# 2022.net
KiCad netlist of a schematic drawn in Altium Designer
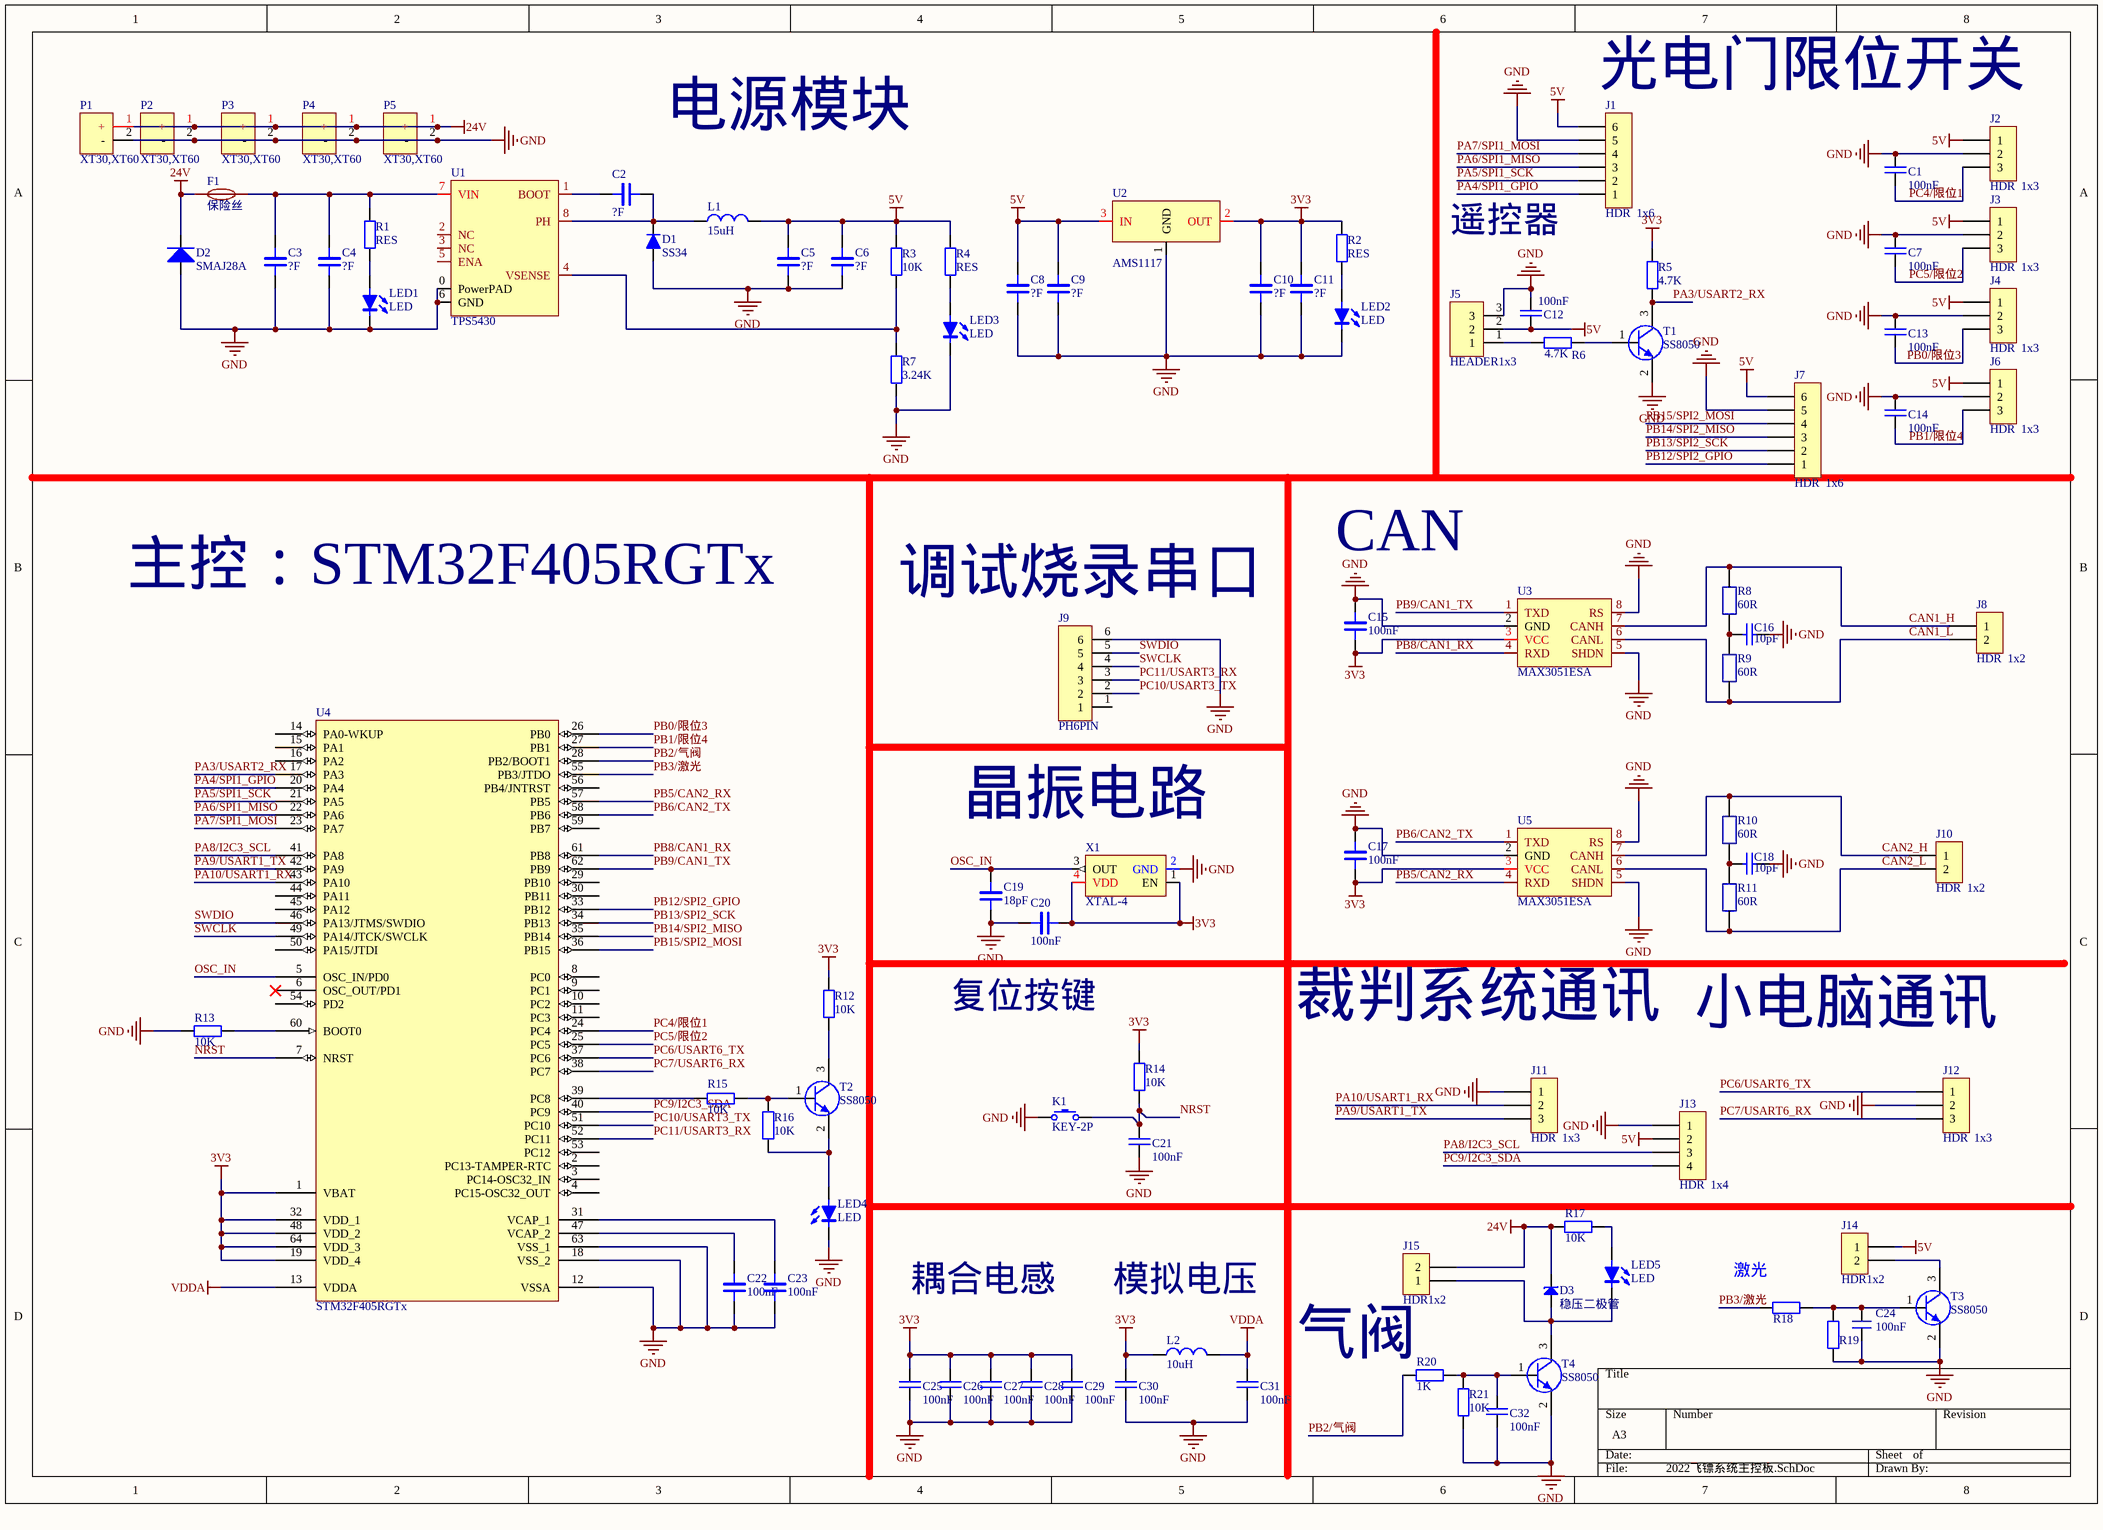
[diagram p0: 2022飞镖系统主控板.SchDoc]

(export (version "E")
  (design (tool "Eeschema 10.0.6"))
  (components
    (comp (ref "C1")
      (value "100nF")
      (footprint "0603_C")
      (fields (field (name "PUBLISHER") "Altium Limited"))
      (libsource (lib "电容-电阻-电感") (part "Cap"))
    )
    (comp (ref "C2")
      (value "?F")
      (footprint "0603_C")
      (description "Capacitor")
      (libsource (lib "General（旧）") (part "CAP"))
    )
    (comp (ref "C3")
      (value "?F")
      (footprint "1206_C")
      (description "Capacitor")
      (libsource (lib "General（旧）") (part "CAP"))
    )
    (comp (ref "C4")
      (value "?F")
      (footprint "1206_C")
      (description "Capacitor")
      (libsource (lib "General（旧）") (part "CAP"))
    )
    (comp (ref "C5")
      (value "?F")
      (footprint "1206_C")
      (description "Capacitor")
      (libsource (lib "General（旧）") (part "CAP"))
    )
    (comp (ref "C6")
      (value "?F")
      (footprint "1206_C")
      (description "Capacitor")
      (libsource (lib "General（旧）") (part "CAP"))
    )
    (comp (ref "C7")
      (value "100nF")
      (footprint "0603_C")
      (fields (field (name "PUBLISHER") "Altium Limited"))
      (libsource (lib "电容-电阻-电感") (part "Cap"))
    )
    (comp (ref "C8")
      (value "?F")
      (footprint "1206_C")
      (description "Capacitor")
      (libsource (lib "General（旧）") (part "CAP"))
    )
    (comp (ref "C9")
      (value "?F")
      (footprint "1206_C")
      (description "Capacitor")
      (libsource (lib "General（旧）") (part "CAP"))
    )
    (comp (ref "C10")
      (value "?F")
      (footprint "1206_C")
      (description "Capacitor")
      (libsource (lib "General（旧）") (part "CAP"))
    )
    (comp (ref "C11")
      (value "?F")
      (footprint "1206_C")
      (description "Capacitor")
      (libsource (lib "General（旧）") (part "CAP"))
    )
    (comp (ref "C12")
      (value "100nF")
      (footprint "0603_C")
      (fields (field (name "PUBLISHER") "Altium Limited"))
      (libsource (lib "电容-电阻-电感") (part "Cap"))
    )
    (comp (ref "C13")
      (value "100nF")
      (footprint "0603_C")
      (fields (field (name "PUBLISHER") "Altium Limited"))
      (libsource (lib "电容-电阻-电感") (part "Cap"))
    )
    (comp (ref "C14")
      (value "100nF")
      (footprint "0603_C")
      (fields (field (name "PUBLISHER") "Altium Limited"))
      (libsource (lib "电容-电阻-电感") (part "Cap"))
    )
    (comp (ref "C15")
      (value "100nF")
      (footprint "0603_C")
      (description "Capacitor")
      (libsource (lib "General（旧）") (part "CAP"))
    )
    (comp (ref "C16") (value "10pF") (footprint "0603_C") (libsource (lib "原理图库") (part "C")))
    (comp (ref "C17")
      (value "100nF")
      (footprint "0603_C")
      (description "Capacitor")
      (libsource (lib "General（旧）") (part "CAP"))
    )
    (comp (ref "C18") (value "10pF") (footprint "0603_C") (libsource (lib "原理图库") (part "C")))
    (comp (ref "C19")
      (value "18pF")
      (footprint "0603_C")
      (description "Capacitor")
      (libsource (lib "General（旧）") (part "CAP"))
    )
    (comp (ref "C20")
      (value "100nF")
      (footprint "0603_C")
      (description "Capacitor")
      (libsource (lib "General（旧）") (part "CAP"))
    )
    (comp (ref "C21")
      (value "100nF")
      (footprint "0603_C")
      (fields (field (name "PUBLISHER") "Altium Limited"))
      (libsource (lib "电容-电阻-电感") (part "Cap"))
    )
    (comp (ref "C22")
      (value "100nF")
      (footprint "0603_C")
      (description "Capacitor")
      (libsource (lib "General（旧）") (part "CAP"))
    )
    (comp (ref "C23")
      (value "100nF")
      (footprint "0603_C")
      (description "Capacitor")
      (libsource (lib "General（旧）") (part "CAP"))
    )
    (comp (ref "C24")
      (value "100nF")
      (footprint "0603_C")
      (fields (field (name "PUBLISHER") "Altium Limited"))
      (libsource (lib "USUAUL") (part "Cap"))
    )
    (comp (ref "C25")
      (value "100nF")
      (footprint "0603_C")
      (fields (field (name "PUBLISHER") "Altium Limited"))
      (libsource (lib "电容-电阻-电感") (part "Cap"))
    )
    (comp (ref "C26")
      (value "100nF")
      (footprint "0603_C")
      (fields (field (name "PUBLISHER") "Altium Limited"))
      (libsource (lib "电容-电阻-电感") (part "Cap"))
    )
    (comp (ref "C27")
      (value "100nF")
      (footprint "0603_C")
      (fields (field (name "PUBLISHER") "Altium Limited"))
      (libsource (lib "电容-电阻-电感") (part "Cap"))
    )
    (comp (ref "C28")
      (value "100nF")
      (footprint "0603_C")
      (fields (field (name "PUBLISHER") "Altium Limited"))
      (libsource (lib "电容-电阻-电感") (part "Cap"))
    )
    (comp (ref "C29")
      (value "100nF")
      (footprint "0603_C")
      (fields (field (name "PUBLISHER") "Altium Limited"))
      (libsource (lib "电容-电阻-电感") (part "Cap"))
    )
    (comp (ref "C30")
      (value "100nF")
      (footprint "0603_C")
      (fields (field (name "PUBLISHER") "Altium Limited"))
      (libsource (lib "电容-电阻-电感") (part "Cap"))
    )
    (comp (ref "C31")
      (value "100nF")
      (footprint "0603_C")
      (fields (field (name "PUBLISHER") "Altium Limited"))
      (libsource (lib "电容-电阻-电感") (part "Cap"))
    )
    (comp (ref "C32")
      (value "100nF")
      (footprint "0603_C")
      (fields (field (name "PUBLISHER") "Altium Limited"))
      (libsource (lib "电容-电阻-电感") (part "Cap"))
    )
    (comp (ref "D1")
      (value "SS34")
      (footprint "SMA(DO-214AC)")
      (description "肖特基二极管")
      (fields
        (field (name "BOM_SUPPLIER PART") "C431540")
        (field (name "BOM_MANUFACTURER PART") "MSK12C02")
        (field (name "CONTRIBUTOR") "LCSC")
      )
      (libsource (lib "General（旧）") (part "SS34"))
    )
    (comp (ref "D2")
      (value "SMAJ28A")
      (footprint "SMA(DO-214AC)")
      (description "TVS")
      (libsource (lib "General（旧）") (part "SMAJ28A"))
    )
    (comp (ref "D3") (value "稳压二极管") (footprint "SOD-323") (libsource (lib "General（旧）") (part "稳压二极管")))
    (comp (ref "F1") (value "保险丝") (footprint "1812_F") (libsource (lib "General（旧）") (part "保险丝")))
    (comp (ref "J1")
      (value "HDR  1x6")
      (footprint "GH 6P 1.25mm 卧 贴")
      (description "Connector")
      (libsource (lib "General（旧）") (part "HDR  1x6"))
    )
    (comp (ref "J2")
      (value "HDR  1x3")
      (footprint "PH 3P 2mm 立 插")
      (description "Connector")
      (libsource (lib "General（旧）") (part "HDR  1x3"))
    )
    (comp (ref "J3")
      (value "HDR  1x3")
      (footprint "PH 3P 2mm 立 插")
      (description "Connector")
      (libsource (lib "General（旧）") (part "HDR  1x3"))
    )
    (comp (ref "J4")
      (value "HDR  1x3")
      (footprint "PH 3P 2mm 立 插")
      (description "Connector")
      (libsource (lib "General（旧）") (part "HDR  1x3"))
    )
    (comp (ref "J5")
      (value "HEADER1x3")
      (footprint "GH 3P 1.25mm 卧 贴")
      (libsource (lib "连接器") (part "HEADER1x3"))
    )
    (comp (ref "J6")
      (value "HDR  1x3")
      (footprint "PH 3P 2mm 立 插")
      (description "Connector")
      (libsource (lib "General（旧）") (part "HDR  1x3"))
    )
    (comp (ref "J7")
      (value "HDR  1x6")
      (footprint "GH 6P 1.25mm 卧 贴")
      (description "Connector")
      (libsource (lib "General（旧）") (part "HDR  1x6"))
    )
    (comp (ref "J8")
      (value "HDR  1x2")
      (footprint "GH 2P 1.25mm 卧 贴")
      (description "Connector")
      (libsource (lib "General（旧）") (part "HDR  1x2"))
    )
    (comp (ref "J9") (value "PH6PIN") (footprint "PH 6P 2mm 立 插") (libsource (lib "连接器") (part "PH 6P")))
    (comp (ref "J10")
      (value "HDR  1x2")
      (footprint "GH 2P 1.25mm 卧 贴")
      (description "Connector")
      (libsource (lib "General（旧）") (part "HDR  1x2"))
    )
    (comp (ref "J11")
      (value "HDR  1x3")
      (footprint "GH 3P 1.25mm 卧 贴")
      (description "Connector")
      (libsource (lib "General（旧）") (part "HDR  1x3"))
    )
    (comp (ref "J12")
      (value "HDR  1x3")
      (footprint "PH 3P 2mm 卧 贴")
      (description "Connector")
      (libsource (lib "General（旧）") (part "HDR  1x3"))
    )
    (comp (ref "J13")
      (value "HDR  1x4")
      (footprint "排针排母 4P 2.54mm")
      (description "Connector")
      (libsource (lib "General（旧）") (part "HDR  1x4"))
    )
    (comp (ref "J14")
      (value "HDR1x2")
      (footprint "PH 2P 2mm 立 贴")
      (description "Connector")
      (libsource (lib "") (part "HDR1x2_1"))
    )
    (comp (ref "J15")
      (value "HDR1x2")
      (footprint "PH 2P 2mm 立 贴")
      (description "Connector")
      (libsource (lib "General") (part "HDR1x2"))
    )
    (comp (ref "K1")
      (value "KEY-2P")
      (footprint "SW-按键")
      (description "Key")
      (libsource (lib "General") (part "KEY-2P"))
    )
    (comp (ref "L1")
      (value "15uH")
      (footprint "SMD_7.3*6.6*3MM_0630")
      (description "Inductor")
      (fields (field (name "PUBLISHER") "Altium Limited"))
      (libsource (lib "General（旧）") (part "Inductor"))
    )
    (comp (ref "L2")
      (value "10uH")
      (footprint "0603_L")
      (description "Inductor")
      (fields (field (name "PUBLISHER") "Altium Limited"))
      (libsource (lib "General（旧）") (part "Inductor"))
    )
    (comp (ref "LED1") (value "LED") (footprint "LED_0603") (libsource (lib "General（旧）") (part "LED")))
    (comp (ref "LED2") (value "LED") (footprint "LED_0603") (libsource (lib "General（旧）") (part "LED")))
    (comp (ref "LED3") (value "LED") (footprint "LED_0603") (libsource (lib "General（旧）") (part "LED")))
    (comp (ref "LED4") (value "LED") (footprint "LED_0603") (libsource (lib "General（旧）") (part "LED")))
    (comp (ref "LED5") (value "LED") (footprint "LED_0603") (libsource (lib "General（旧）") (part "LED")))
    (comp (ref "P1")
      (value "XT30,XT60")
      (footprint "XT30PW-F")
      (description "电源接口")
      (libsource (lib "General（旧）") (part "XT"))
    )
    (comp (ref "P2")
      (value "XT30,XT60")
      (footprint "XT30PW-F")
      (description "电源接口")
      (libsource (lib "General（旧）") (part "XT"))
    )
    (comp (ref "P3")
      (value "XT30,XT60")
      (footprint "XT30PW-F")
      (description "电源接口")
      (libsource (lib "General（旧）") (part "XT"))
    )
    (comp (ref "P4")
      (value "XT30,XT60")
      (footprint "XT30PW-F")
      (description "电源接口")
      (libsource (lib "General（旧）") (part "XT"))
    )
    (comp (ref "P5")
      (value "XT30,XT60")
      (footprint "XT30PW-F")
      (description "电源接口")
      (libsource (lib "General（旧）") (part "XT"))
    )
    (comp (ref "R1")
      (value "RES")
      (footprint "0603_R")
      (description "Resistor")
      (libsource (lib "") (part "RES_1"))
    )
    (comp (ref "R2")
      (value "RES")
      (footprint "0603_R")
      (description "Resistor")
      (libsource (lib "") (part "RES_1"))
    )
    (comp (ref "R3")
      (value "10K")
      (footprint "0603_R")
      (description "Resistor")
      (libsource (lib "") (part "RES_1"))
    )
    (comp (ref "R4")
      (value "RES")
      (footprint "0603_R")
      (description "Resistor")
      (libsource (lib "") (part "RES_1"))
    )
    (comp (ref "R5")
      (value "4.7K")
      (footprint "0603_R")
      (fields (field (name "PUBLISHER") "Altium Limited"))
      (libsource (lib "电容-电阻-电感") (part "Res"))
    )
    (comp (ref "R6")
      (value "4.7K")
      (footprint "0603_R")
      (fields (field (name "PUBLISHER") "Altium Limited"))
      (libsource (lib "") (part "Res_2"))
    )
    (comp (ref "R7")
      (value "3.24K")
      (footprint "0603_R")
      (description "Resistor")
      (libsource (lib "") (part "RES_1"))
    )
    (comp (ref "R8") (value "60R") (footprint "0603_R") (libsource (lib "原理图库") (part "R")))
    (comp (ref "R9") (value "60R") (footprint "0603_R") (libsource (lib "原理图库") (part "R")))
    (comp (ref "R10") (value "60R") (footprint "0603_R") (libsource (lib "原理图库") (part "R")))
    (comp (ref "R11") (value "60R") (footprint "0603_R") (libsource (lib "原理图库") (part "R")))
    (comp (ref "R12")
      (value "10K")
      (footprint "0603_R")
      (description "Resistor")
      (libsource (lib "") (part "RES_2"))
    )
    (comp (ref "R13")
      (value "10K")
      (footprint "0603_R")
      (description "Resistor")
      (libsource (lib "") (part "RES_3"))
    )
    (comp (ref "R14")
      (value "10K")
      (footprint "0603_R")
      (fields (field (name "PUBLISHER") "Altium Limited"))
      (libsource (lib "电容-电阻-电感") (part "Res"))
    )
    (comp (ref "R15")
      (value "10K")
      (footprint "0603_R")
      (description "Resistor")
      (libsource (lib "General（旧）") (part "RES"))
    )
    (comp (ref "R16")
      (value "10K")
      (footprint "0603_R")
      (description "Resistor")
      (libsource (lib "") (part "RES_3"))
    )
    (comp (ref "R17")
      (value "10K")
      (footprint "0603_R")
      (fields (field (name "PUBLISHER") "Altium Limited"))
      (libsource (lib "") (part "Res_1"))
    )
    (comp (ref "R18")
      (value "Res")
      (footprint "0603_R")
      (fields (field (name "PUBLISHER") "Altium Limited"))
      (libsource (lib "") (part "Res_1"))
    )
    (comp (ref "R19")
      (value "Res")
      (footprint "0603_R")
      (fields (field (name "PUBLISHER") "Altium Limited"))
      (libsource (lib "电容-电阻-电感") (part "Res"))
    )
    (comp (ref "R20")
      (value "1K")
      (footprint "0603_R")
      (fields (field (name "PUBLISHER") "Altium Limited"))
      (libsource (lib "") (part "Res_1"))
    )
    (comp (ref "R21")
      (value "10K")
      (footprint "0603_R")
      (fields (field (name "PUBLISHER") "Altium Limited"))
      (libsource (lib "电容-电阻-电感") (part "Res"))
    )
    (comp (ref "T1")
      (value "SS8050")
      (footprint "SOT-23")
      (description "NPN")
      (fields (field (name "PUBLISHER") "Altium Limited"))
      (libsource (lib "二极管-晶体管") (part "SS8050"))
    )
    (comp (ref "T2")
      (value "SS8050")
      (footprint "SOT-23")
      (description "NPN")
      (fields (field (name "PUBLISHER") "Altium Limited"))
      (libsource (lib "二极管-晶体管") (part "SS8050"))
    )
    (comp (ref "T3")
      (value "SS8050")
      (footprint "SOT-23")
      (description "NPN")
      (fields (field (name "PUBLISHER") "Altium Limited"))
      (libsource (lib "二极管-晶体管") (part "SS8050"))
    )
    (comp (ref "T4")
      (value "SS8050")
      (footprint "SOT-23")
      (description "NPN")
      (fields (field (name "PUBLISHER") "Altium Limited"))
      (libsource (lib "二极管-晶体管") (part "SS8050"))
    )
    (comp (ref "U1")
      (value "TPS5430")
      (footprint "SOP8-EP")
      (description "DC-DC 降压芯片")
      (libsource (lib "General（旧）") (part "TPS5430"))
    )
    (comp (ref "U2")
      (value "AMS1117")
      (footprint "SOT-223")
      (description "LDO")
      (libsource (lib "General（旧）") (part "AMS1117"))
    )
    (comp (ref "U3")
      (value "MAX3051ESA")
      (footprint "SOP8")
      (description "CAN芯片")
      (libsource (lib "General（旧）") (part "MAX3051ESA"))
    )
    (comp (ref "U4")
      (value "STM32F405RGTx")
      (footprint "LQFP-64_10x10x05P")
      (description "STM32单片机")
      (libsource (lib "General（旧）") (part "STM32F405RGTx"))
    )
    (comp (ref "U5")
      (value "MAX3051ESA")
      (footprint "SOP8")
      (description "CAN芯片")
      (libsource (lib "General（旧）") (part "MAX3051ESA"))
    )
    (comp (ref "X1")
      (value "XTAL-4")
      (footprint "OSC-SMD_4P")
      (description "Oscillator")
      (libsource (lib "General（旧）") (part "XTAL-4"))
    )
  )
  (nets
    (net (code "1") (name "/CAN1_H") (class "Default")
      (node (ref "J8") (pin "1") (pinfunction "1_1") (pintype "passive"))
      (node (ref "R8") (pin "2") (pinfunction "2_2") (pintype "passive"))
      (node (ref "U3") (pin "7") (pinfunction "CANH_7") (pintype "passive"))
    )
    (net (code "2") (name "/CAN1_L") (class "Default")
      (node (ref "J8") (pin "2") (pinfunction "2_2") (pintype "passive"))
      (node (ref "R9") (pin "2") (pinfunction "2_2") (pintype "passive"))
      (node (ref "U3") (pin "6") (pinfunction "CANL_6") (pintype "passive"))
    )
    (net (code "3") (name "/CAN2_H") (class "Default")
      (node (ref "J10") (pin "1") (pinfunction "1_1") (pintype "passive"))
      (node (ref "R10") (pin "2") (pinfunction "2_2") (pintype "passive"))
      (node (ref "U5") (pin "7") (pinfunction "CANH_7") (pintype "passive"))
    )
    (net (code "4") (name "/CAN2_L") (class "Default")
      (node (ref "J10") (pin "2") (pinfunction "2_2") (pintype "passive"))
      (node (ref "R11") (pin "2") (pinfunction "2_2") (pintype "passive"))
      (node (ref "U5") (pin "6") (pinfunction "CANL_6") (pintype "passive"))
    )
    (net (code "5") (name "/NRST") (class "Default")
      (node (ref "C21") (pin "1") (pinfunction "1_1") (pintype "passive"))
      (node (ref "K1") (pin "2") (pinfunction "2_2") (pintype "passive"))
      (node (ref "R14") (pin "1") (pinfunction "1_1") (pintype "passive"))
      (node (ref "U4") (pin "7") (pinfunction "NRST_7") (pintype "bidirectional"))
    )
    (net (code "6") (name "/OSC_IN") (class "Default")
      (node (ref "C19") (pin "2") (pinfunction "2_2") (pintype "passive"))
      (node (ref "U4") (pin "5") (pinfunction "OSC_IN/PD0_5") (pintype "passive"))
      (node (ref "X1") (pin "3") (pinfunction "OUT_3") (pintype "output"))
    )
    (net (code "7") (name "/PA3{slash}USART2_RX") (class "Default")
      (node (ref "R5") (pin "1") (pinfunction "1_1") (pintype "passive"))
      (node (ref "T1") (pin "3") (pinfunction "C_3") (pintype "passive"))
      (node (ref "U4") (pin "17") (pinfunction "PA3_17") (pintype "bidirectional"))
    )
    (net (code "8") (name "/PA4{slash}SPI1_GPIO") (class "Default")
      (node (ref "J1") (pin "1") (pinfunction "1_1") (pintype "passive"))
      (node (ref "U4") (pin "20") (pinfunction "PA4_20") (pintype "bidirectional"))
    )
    (net (code "9") (name "/PA5{slash}SPI1_SCK") (class "Default")
      (node (ref "J1") (pin "2") (pinfunction "2_2") (pintype "passive"))
      (node (ref "U4") (pin "21") (pinfunction "PA5_21") (pintype "bidirectional"))
    )
    (net (code "10") (name "/PA6{slash}SPI1_MISO") (class "Default")
      (node (ref "J1") (pin "3") (pinfunction "3_3") (pintype "passive"))
      (node (ref "U4") (pin "22") (pinfunction "PA6_22") (pintype "bidirectional"))
    )
    (net (code "11") (name "/PA7{slash}SPI1_MOSI") (class "Default")
      (node (ref "J1") (pin "4") (pinfunction "4_4") (pintype "passive"))
      (node (ref "U4") (pin "23") (pinfunction "PA7_23") (pintype "bidirectional"))
    )
    (net (code "12") (name "/PA8{slash}I2C3_SCL") (class "Default")
      (node (ref "J13") (pin "3") (pinfunction "3_3") (pintype "passive"))
      (node (ref "U4") (pin "41") (pinfunction "PA8_41") (pintype "bidirectional"))
    )
    (net (code "13") (name "/PA9{slash}USART1_TX") (class "Default")
      (node (ref "J11") (pin "3") (pinfunction "3_3") (pintype "passive"))
      (node (ref "U4") (pin "42") (pinfunction "PA9_42") (pintype "bidirectional"))
    )
    (net (code "14") (name "/PA10{slash}USART1_RX") (class "Default")
      (node (ref "J11") (pin "2") (pinfunction "2_2") (pintype "passive"))
      (node (ref "U4") (pin "43") (pinfunction "PA10_43") (pintype "bidirectional"))
    )
    (net (code "15") (name "/PB0{slash}限位3") (class "Default")
      (node (ref "C13") (pin "2") (pinfunction "2_2") (pintype "passive"))
      (node (ref "J4") (pin "3") (pinfunction "3_3") (pintype "passive"))
      (node (ref "U4") (pin "26") (pinfunction "PB0_26") (pintype "bidirectional"))
    )
    (net (code "16") (name "/PB1{slash}限位4") (class "Default")
      (node (ref "C14") (pin "2") (pinfunction "2_2") (pintype "passive"))
      (node (ref "J6") (pin "3") (pinfunction "3_3") (pintype "passive"))
      (node (ref "U4") (pin "27") (pinfunction "PB1_27") (pintype "bidirectional"))
    )
    (net (code "17") (name "/PB2{slash}气阀") (class "Default")
      (node (ref "R20") (pin "1") (pinfunction "1_1") (pintype "passive"))
      (node (ref "U4") (pin "28") (pinfunction "PB2/BOOT1_28") (pintype "bidirectional"))
    )
    (net (code "18") (name "/PB3{slash}激光") (class "Default")
      (node (ref "R18") (pin "1") (pinfunction "1_1") (pintype "passive"))
      (node (ref "U4") (pin "55") (pinfunction "PB3/JTDO_55") (pintype "bidirectional"))
    )
    (net (code "19") (name "/PB5{slash}CAN2_RX") (class "Default")
      (node (ref "U4") (pin "57") (pinfunction "PB5_57") (pintype "bidirectional"))
      (node (ref "U5") (pin "4") (pinfunction "RXD_4") (pintype "passive"))
    )
    (net (code "20") (name "/PB6{slash}CAN2_TX") (class "Default")
      (node (ref "U4") (pin "58") (pinfunction "PB6_58") (pintype "bidirectional"))
      (node (ref "U5") (pin "1") (pinfunction "TXD_1") (pintype "passive"))
    )
    (net (code "21") (name "/PB8{slash}CAN1_RX") (class "Default")
      (node (ref "U3") (pin "4") (pinfunction "RXD_4") (pintype "passive"))
      (node (ref "U4") (pin "61") (pinfunction "PB8_61") (pintype "bidirectional"))
    )
    (net (code "22") (name "/PB9{slash}CAN1_TX") (class "Default")
      (node (ref "U3") (pin "1") (pinfunction "TXD_1") (pintype "passive"))
      (node (ref "U4") (pin "62") (pinfunction "PB9_62") (pintype "bidirectional"))
    )
    (net (code "23") (name "/PB12{slash}SPI2_GPIO") (class "Default")
      (node (ref "J7") (pin "1") (pinfunction "1_1") (pintype "passive"))
      (node (ref "U4") (pin "33") (pinfunction "PB12_33") (pintype "bidirectional"))
    )
    (net (code "24") (name "/PB13{slash}SPI2_SCK") (class "Default")
      (node (ref "J7") (pin "2") (pinfunction "2_2") (pintype "passive"))
      (node (ref "U4") (pin "34") (pinfunction "PB13_34") (pintype "bidirectional"))
    )
    (net (code "25") (name "/PB14{slash}SPI2_MISO") (class "Default")
      (node (ref "J7") (pin "3") (pinfunction "3_3") (pintype "passive"))
      (node (ref "U4") (pin "35") (pinfunction "PB14_35") (pintype "bidirectional"))
    )
    (net (code "26") (name "/PB15{slash}SPI2_MOSI") (class "Default")
      (node (ref "J7") (pin "4") (pinfunction "4_4") (pintype "passive"))
      (node (ref "U4") (pin "36") (pinfunction "PB15_36") (pintype "bidirectional"))
    )
    (net (code "27") (name "/PC4{slash}限位1") (class "Default")
      (node (ref "C1") (pin "2") (pinfunction "2_2") (pintype "passive"))
      (node (ref "J2") (pin "3") (pinfunction "3_3") (pintype "passive"))
      (node (ref "U4") (pin "24") (pinfunction "PC4_24") (pintype "bidirectional"))
    )
    (net (code "28") (name "/PC5{slash}限位2") (class "Default")
      (node (ref "C7") (pin "2") (pinfunction "2_2") (pintype "passive"))
      (node (ref "J3") (pin "3") (pinfunction "3_3") (pintype "passive"))
      (node (ref "U4") (pin "25") (pinfunction "PC5_25") (pintype "bidirectional"))
    )
    (net (code "29") (name "/PC6{slash}USART6_TX") (class "Default")
      (node (ref "J12") (pin "1") (pinfunction "1_1") (pintype "passive"))
      (node (ref "U4") (pin "37") (pinfunction "PC6_37") (pintype "bidirectional"))
    )
    (net (code "30") (name "/PC7{slash}USART6_RX") (class "Default")
      (node (ref "J12") (pin "3") (pinfunction "3_3") (pintype "passive"))
      (node (ref "U4") (pin "38") (pinfunction "PC7_38") (pintype "bidirectional"))
    )
    (net (code "31") (name "/PC9{slash}I2C3_SDA") (class "Default")
      (node (ref "J13") (pin "4") (pinfunction "4_4") (pintype "passive"))
      (node (ref "U4") (pin "40") (pinfunction "PC9_40") (pintype "bidirectional"))
    )
    (net (code "32") (name "/PC10{slash}USART3_TX") (class "Default")
      (node (ref "J9") (pin "2") (pinfunction "2_2") (pintype "passive"))
      (node (ref "U4") (pin "51") (pinfunction "PC10_51") (pintype "bidirectional"))
    )
    (net (code "33") (name "/PC11{slash}USART3_RX") (class "Default")
      (node (ref "J9") (pin "3") (pinfunction "3_3") (pintype "passive"))
      (node (ref "U4") (pin "52") (pinfunction "PC11_52") (pintype "bidirectional"))
    )
    (net (code "34") (name "/SWCLK") (class "Default")
      (node (ref "J9") (pin "4") (pinfunction "4_4") (pintype "passive"))
      (node (ref "U4") (pin "49") (pinfunction "PA14/JTCK/SWCLK_49") (pintype "bidirectional"))
    )
    (net (code "35") (name "/SWDIO") (class "Default")
      (node (ref "J9") (pin "5") (pinfunction "5_5") (pintype "passive"))
      (node (ref "U4") (pin "46") (pinfunction "PA13/JTMS/SWDIO_46") (pintype "bidirectional"))
    )
    (net (code "36") (name "3V3") (class "Default")
      (node (ref "C10") (pin "2") (pinfunction "2_2") (pintype "passive"))
      (node (ref "C11") (pin "2") (pinfunction "2_2") (pintype "passive"))
      (node (ref "C15") (pin "2") (pinfunction "2_2") (pintype "passive"))
      (node (ref "C17") (pin "2") (pinfunction "2_2") (pintype "passive"))
      (node (ref "C20") (pin "2") (pinfunction "2_2") (pintype "passive"))
      (node (ref "C25") (pin "1") (pinfunction "1_1") (pintype "passive"))
      (node (ref "C26") (pin "1") (pinfunction "1_1") (pintype "passive"))
      (node (ref "C27") (pin "1") (pinfunction "1_1") (pintype "passive"))
      (node (ref "C28") (pin "1") (pinfunction "1_1") (pintype "passive"))
      (node (ref "C29") (pin "1") (pinfunction "1_1") (pintype "passive"))
      (node (ref "C30") (pin "1") (pinfunction "1_1") (pintype "passive"))
      (node (ref "L2") (pin "1") (pinfunction "1_1") (pintype "passive"))
      (node (ref "R12") (pin "1") (pinfunction "1_1") (pintype "passive"))
      (node (ref "R14") (pin "2") (pinfunction "2_2") (pintype "passive"))
      (node (ref "R2") (pin "2") (pinfunction "2_2") (pintype "passive"))
      (node (ref "R5") (pin "2") (pinfunction "2_2") (pintype "passive"))
      (node (ref "U2") (pin "2") (pinfunction "OUT_2") (pintype "passive"))
      (node (ref "U3") (pin "3") (pinfunction "VCC_3") (pintype "passive"))
      (node (ref "U4") (pin "1") (pinfunction "VBAT_1") (pintype "power_in"))
      (node (ref "U4") (pin "19") (pinfunction "VDD_4_19") (pintype "power_in"))
      (node (ref "U4") (pin "32") (pinfunction "VDD_1_32") (pintype "power_in"))
      (node (ref "U4") (pin "48") (pinfunction "VDD_2_48") (pintype "power_in"))
      (node (ref "U4") (pin "64") (pinfunction "VDD_3_64") (pintype "power_in"))
      (node (ref "U5") (pin "3") (pinfunction "VCC_3") (pintype "passive"))
      (node (ref "X1") (pin "1") (pinfunction "EN_1") (pintype "passive"))
      (node (ref "X1") (pin "4") (pinfunction "VDD_4") (pintype "power_in"))
    )
    (net (code "37") (name "5V") (class "Default")
      (node (ref "C12") (pin "1") (pinfunction "1_1") (pintype "passive"))
      (node (ref "C5") (pin "2") (pinfunction "2_2") (pintype "passive"))
      (node (ref "C6") (pin "2") (pinfunction "2_2") (pintype "passive"))
      (node (ref "C8") (pin "2") (pinfunction "2_2") (pintype "passive"))
      (node (ref "C9") (pin "2") (pinfunction "2_2") (pintype "passive"))
      (node (ref "J1") (pin "6") (pinfunction "6_6") (pintype "passive"))
      (node (ref "J13") (pin "2") (pinfunction "2_2") (pintype "passive"))
      (node (ref "J14") (pin "1") (pinfunction "1_1") (pintype "passive"))
      (node (ref "J2") (pin "1") (pinfunction "1_1") (pintype "passive"))
      (node (ref "J3") (pin "1") (pinfunction "1_1") (pintype "passive"))
      (node (ref "J4") (pin "1") (pinfunction "1_1") (pintype "passive"))
      (node (ref "J5") (pin "2") (pinfunction "2_2") (pintype "passive"))
      (node (ref "J6") (pin "1") (pinfunction "1_1") (pintype "passive"))
      (node (ref "J7") (pin "6") (pinfunction "6_6") (pintype "passive"))
      (node (ref "L1") (pin "2") (pinfunction "2_2") (pintype "passive"))
      (node (ref "R3") (pin "2") (pinfunction "2_2") (pintype "passive"))
      (node (ref "R4") (pin "2") (pinfunction "2_2") (pintype "passive"))
      (node (ref "U2") (pin "3") (pinfunction "IN_3") (pintype "passive"))
    )
    (net (code "38") (name "24V") (class "Default")
      (node (ref "D2") (pin "2") (pinfunction "K_2") (pintype "passive"))
      (node (ref "D3") (pin "2") (pinfunction "K_2") (pintype "passive"))
      (node (ref "F1") (pin "1") (pinfunction "1_1") (pintype "passive"))
      (node (ref "J15") (pin "2") (pinfunction "2_2") (pintype "passive"))
      (node (ref "P1") (pin "1") (pinfunction "+_1") (pintype "passive"))
      (node (ref "P2") (pin "1") (pinfunction "+_1") (pintype "passive"))
      (node (ref "P3") (pin "1") (pinfunction "+_1") (pintype "passive"))
      (node (ref "P4") (pin "1") (pinfunction "+_1") (pintype "passive"))
      (node (ref "P5") (pin "1") (pinfunction "+_1") (pintype "passive"))
      (node (ref "R17") (pin "1") (pinfunction "1_1") (pintype "passive"))
    )
    (net (code "39") (name "GND") (class "Default")
      (node (ref "C1") (pin "1") (pinfunction "1_1") (pintype "passive"))
      (node (ref "C10") (pin "1") (pinfunction "1_1") (pintype "passive"))
      (node (ref "C11") (pin "1") (pinfunction "1_1") (pintype "passive"))
      (node (ref "C12") (pin "2") (pinfunction "2_2") (pintype "passive"))
      (node (ref "C13") (pin "1") (pinfunction "1_1") (pintype "passive"))
      (node (ref "C14") (pin "1") (pinfunction "1_1") (pintype "passive"))
      (node (ref "C15") (pin "1") (pinfunction "1_1") (pintype "passive"))
      (node (ref "C16") (pin "2") (pinfunction "2_2") (pintype "passive"))
      (node (ref "C17") (pin "1") (pinfunction "1_1") (pintype "passive"))
      (node (ref "C18") (pin "2") (pinfunction "2_2") (pintype "passive"))
      (node (ref "C19") (pin "1") (pinfunction "1_1") (pintype "passive"))
      (node (ref "C20") (pin "1") (pinfunction "1_1") (pintype "passive"))
      (node (ref "C21") (pin "2") (pinfunction "2_2") (pintype "passive"))
      (node (ref "C22") (pin "1") (pinfunction "1_1") (pintype "passive"))
      (node (ref "C23") (pin "1") (pinfunction "1_1") (pintype "passive"))
      (node (ref "C24") (pin "1") (pinfunction "1_1") (pintype "passive"))
      (node (ref "C25") (pin "2") (pinfunction "2_2") (pintype "passive"))
      (node (ref "C26") (pin "2") (pinfunction "2_2") (pintype "passive"))
      (node (ref "C27") (pin "2") (pinfunction "2_2") (pintype "passive"))
      (node (ref "C28") (pin "2") (pinfunction "2_2") (pintype "passive"))
      (node (ref "C29") (pin "2") (pinfunction "2_2") (pintype "passive"))
      (node (ref "C3") (pin "1") (pinfunction "1_1") (pintype "passive"))
      (node (ref "C30") (pin "2") (pinfunction "2_2") (pintype "passive"))
      (node (ref "C31") (pin "2") (pinfunction "2_2") (pintype "passive"))
      (node (ref "C32") (pin "2") (pinfunction "2_2") (pintype "passive"))
      (node (ref "C4") (pin "1") (pinfunction "1_1") (pintype "passive"))
      (node (ref "C5") (pin "1") (pinfunction "1_1") (pintype "passive"))
      (node (ref "C6") (pin "1") (pinfunction "1_1") (pintype "passive"))
      (node (ref "C7") (pin "1") (pinfunction "1_1") (pintype "passive"))
      (node (ref "C8") (pin "1") (pinfunction "1_1") (pintype "passive"))
      (node (ref "C9") (pin "1") (pinfunction "1_1") (pintype "passive"))
      (node (ref "D1") (pin "1") (pinfunction "1_1") (pintype "passive"))
      (node (ref "D2") (pin "1") (pinfunction "A_1") (pintype "passive"))
      (node (ref "J1") (pin "5") (pinfunction "5_5") (pintype "passive"))
      (node (ref "J11") (pin "1") (pinfunction "1_1") (pintype "passive"))
      (node (ref "J12") (pin "2") (pinfunction "2_2") (pintype "passive"))
      (node (ref "J13") (pin "1") (pinfunction "1_1") (pintype "passive"))
      (node (ref "J2") (pin "2") (pinfunction "2_2") (pintype "passive"))
      (node (ref "J3") (pin "2") (pinfunction "2_2") (pintype "passive"))
      (node (ref "J4") (pin "2") (pinfunction "2_2") (pintype "passive"))
      (node (ref "J5") (pin "3") (pinfunction "3_3") (pintype "passive"))
      (node (ref "J6") (pin "2") (pinfunction "2_2") (pintype "passive"))
      (node (ref "J7") (pin "5") (pinfunction "5_5") (pintype "passive"))
      (node (ref "J9") (pin "6") (pinfunction "6_6") (pintype "passive"))
      (node (ref "K1") (pin "1") (pinfunction "1_1") (pintype "passive"))
      (node (ref "LED1") (pin "2") (pinfunction "C_2") (pintype "passive"))
      (node (ref "LED2") (pin "2") (pinfunction "C_2") (pintype "passive"))
      (node (ref "LED3") (pin "2") (pinfunction "C_2") (pintype "passive"))
      (node (ref "LED4") (pin "2") (pinfunction "C_2") (pintype "passive"))
      (node (ref "P1") (pin "2") (pinfunction "-_2") (pintype "passive"))
      (node (ref "P2") (pin "2") (pinfunction "-_2") (pintype "passive"))
      (node (ref "P3") (pin "2") (pinfunction "-_2") (pintype "passive"))
      (node (ref "P4") (pin "2") (pinfunction "-_2") (pintype "passive"))
      (node (ref "P5") (pin "2") (pinfunction "-_2") (pintype "passive"))
      (node (ref "R13") (pin "1") (pinfunction "1_1") (pintype "passive"))
      (node (ref "R19") (pin "1") (pinfunction "1_1") (pintype "passive"))
      (node (ref "R21") (pin "1") (pinfunction "1_1") (pintype "passive"))
      (node (ref "R7") (pin "1") (pinfunction "1_1") (pintype "passive"))
      (node (ref "T1") (pin "2") (pinfunction "E_2") (pintype "passive"))
      (node (ref "T3") (pin "2") (pinfunction "E_2") (pintype "passive"))
      (node (ref "T4") (pin "2") (pinfunction "E_2") (pintype "passive"))
      (node (ref "U1") (pin "0") (pinfunction "PowerPAD_0") (pintype "passive"))
      (node (ref "U1") (pin "6") (pinfunction "GND_6") (pintype "passive"))
      (node (ref "U2") (pin "1") (pinfunction "GND_1") (pintype "passive"))
      (node (ref "U3") (pin "2") (pinfunction "GND_2") (pintype "passive"))
      (node (ref "U3") (pin "5") (pinfunction "SHDN_5") (pintype "passive"))
      (node (ref "U3") (pin "8") (pinfunction "RS_8") (pintype "passive"))
      (node (ref "U4") (pin "12") (pinfunction "VSSA_12") (pintype "passive"))
      (node (ref "U4") (pin "18") (pinfunction "VSS_2_18") (pintype "passive"))
      (node (ref "U4") (pin "63") (pinfunction "VSS_1_63") (pintype "passive"))
      (node (ref "U5") (pin "2") (pinfunction "GND_2") (pintype "passive"))
      (node (ref "U5") (pin "5") (pinfunction "SHDN_5") (pintype "passive"))
      (node (ref "U5") (pin "8") (pinfunction "RS_8") (pintype "passive"))
      (node (ref "X1") (pin "2") (pinfunction "GND_2") (pintype "passive"))
    )
    (net (code "40") (name "Net-(C16-Pad1)") (class "Default")
      (node (ref "C16") (pin "1") (pinfunction "1_1") (pintype "passive"))
      (node (ref "R8") (pin "1") (pinfunction "1_1") (pintype "passive"))
      (node (ref "R9") (pin "1") (pinfunction "1_1") (pintype "passive"))
    )
    (net (code "41") (name "Net-(C18-Pad1)") (class "Default")
      (node (ref "C18") (pin "1") (pinfunction "1_1") (pintype "passive"))
      (node (ref "R10") (pin "1") (pinfunction "1_1") (pintype "passive"))
      (node (ref "R11") (pin "1") (pinfunction "1_1") (pintype "passive"))
    )
    (net (code "42") (name "Net-(D3-A)") (class "Default")
      (node (ref "D3") (pin "1") (pinfunction "A_1") (pintype "passive"))
      (node (ref "J15") (pin "1") (pinfunction "1_1") (pintype "passive"))
      (node (ref "LED5") (pin "2") (pinfunction "C_2") (pintype "passive"))
      (node (ref "T4") (pin "3") (pinfunction "C_3") (pintype "passive"))
    )
    (net (code "43") (name "Net-(J5-Pad1)") (class "Default")
      (node (ref "J5") (pin "1") (pinfunction "1_1") (pintype "power_in"))
      (node (ref "R6") (pin "2") (pinfunction "2_2") (pintype "passive"))
    )
    (net (code "44") (name "Net-(LED1-A)") (class "Default")
      (node (ref "LED1") (pin "1") (pinfunction "A_1") (pintype "passive"))
      (node (ref "R1") (pin "1") (pinfunction "1_1") (pintype "passive"))
    )
    (net (code "45") (name "Net-(LED2-A)") (class "Default")
      (node (ref "LED2") (pin "1") (pinfunction "A_1") (pintype "passive"))
      (node (ref "R2") (pin "1") (pinfunction "1_1") (pintype "passive"))
    )
    (net (code "46") (name "Net-(LED3-A)") (class "Default")
      (node (ref "LED3") (pin "1") (pinfunction "A_1") (pintype "passive"))
      (node (ref "R4") (pin "1") (pinfunction "1_1") (pintype "passive"))
    )
    (net (code "47") (name "Net-(LED4-A)") (class "Default")
      (node (ref "LED4") (pin "1") (pinfunction "A_1") (pintype "passive"))
      (node (ref "R16") (pin "1") (pinfunction "1_1") (pintype "passive"))
      (node (ref "T2") (pin "2") (pinfunction "E_2") (pintype "passive"))
    )
    (net (code "48") (name "Net-(LED5-A)") (class "Default")
      (node (ref "LED5") (pin "1") (pinfunction "A_1") (pintype "passive"))
      (node (ref "R17") (pin "2") (pinfunction "2_2") (pintype "passive"))
    )
    (net (code "49") (name "Net-(T1-B)") (class "Default")
      (node (ref "R6") (pin "1") (pinfunction "1_1") (pintype "passive"))
      (node (ref "T1") (pin "1") (pinfunction "B_1") (pintype "passive"))
    )
    (net (code "50") (name "Net-(T2-B)") (class "Default")
      (node (ref "R15") (pin "1") (pinfunction "1_1") (pintype "passive"))
      (node (ref "R16") (pin "2") (pinfunction "2_2") (pintype "passive"))
      (node (ref "T2") (pin "1") (pinfunction "B_1") (pintype "passive"))
    )
    (net (code "51") (name "Net-(T2-C)") (class "Default")
      (node (ref "R12") (pin "2") (pinfunction "2_2") (pintype "passive"))
      (node (ref "T2") (pin "3") (pinfunction "C_3") (pintype "passive"))
    )
    (net (code "52") (name "Net-(T3-B)") (class "Default")
      (node (ref "C24") (pin "2") (pinfunction "2_2") (pintype "passive"))
      (node (ref "R18") (pin "2") (pinfunction "2_2") (pintype "passive"))
      (node (ref "R19") (pin "2") (pinfunction "2_2") (pintype "passive"))
      (node (ref "T3") (pin "1") (pinfunction "B_1") (pintype "passive"))
    )
    (net (code "53") (name "Net-(T3-C)") (class "Default")
      (node (ref "J14") (pin "2") (pinfunction "2_2") (pintype "passive"))
      (node (ref "T3") (pin "3") (pinfunction "C_3") (pintype "passive"))
    )
    (net (code "54") (name "Net-(T4-B)") (class "Default")
      (node (ref "C32") (pin "1") (pinfunction "1_1") (pintype "passive"))
      (node (ref "R20") (pin "2") (pinfunction "2_2") (pintype "passive"))
      (node (ref "R21") (pin "2") (pinfunction "2_2") (pintype "passive"))
      (node (ref "T4") (pin "1") (pinfunction "B_1") (pintype "passive"))
    )
    (net (code "55") (name "Net-(U1-BOOT)") (class "Default")
      (node (ref "C2") (pin "1") (pinfunction "1_1") (pintype "passive"))
      (node (ref "U1") (pin "1") (pinfunction "BOOT_1") (pintype "passive"))
    )
    (net (code "56") (name "Net-(U1-PH)") (class "Default")
      (node (ref "C2") (pin "2") (pinfunction "2_2") (pintype "passive"))
      (node (ref "D1") (pin "2") (pinfunction "2_2") (pintype "passive"))
      (node (ref "L1") (pin "1") (pinfunction "1_1") (pintype "passive"))
      (node (ref "U1") (pin "8") (pinfunction "PH_8") (pintype "passive"))
    )
    (net (code "57") (name "Net-(U1-VIN)") (class "Default")
      (node (ref "C3") (pin "2") (pinfunction "2_2") (pintype "passive"))
      (node (ref "C4") (pin "2") (pinfunction "2_2") (pintype "passive"))
      (node (ref "F1") (pin "2") (pinfunction "2_2") (pintype "passive"))
      (node (ref "R1") (pin "2") (pinfunction "2_2") (pintype "passive"))
      (node (ref "U1") (pin "7") (pinfunction "VIN_7") (pintype "passive"))
    )
    (net (code "58") (name "Net-(U1-VSENSE)") (class "Default")
      (node (ref "R3") (pin "1") (pinfunction "1_1") (pintype "passive"))
      (node (ref "R7") (pin "2") (pinfunction "2_2") (pintype "passive"))
      (node (ref "U1") (pin "4") (pinfunction "VSENSE_4") (pintype "passive"))
    )
    (net (code "59") (name "Net-(U4-BOOT0)") (class "Default")
      (node (ref "R13") (pin "2") (pinfunction "2_2") (pintype "passive"))
      (node (ref "U4") (pin "60") (pinfunction "BOOT0_60") (pintype "input"))
    )
    (net (code "60") (name "Net-(U4-PC8)") (class "Default")
      (node (ref "R15") (pin "2") (pinfunction "2_2") (pintype "passive"))
      (node (ref "U4") (pin "39") (pinfunction "PC8_39") (pintype "bidirectional"))
    )
    (net (code "61") (name "Net-(U4-VCAP_1)") (class "Default")
      (node (ref "C23") (pin "2") (pinfunction "2_2") (pintype "passive"))
      (node (ref "U4") (pin "31") (pinfunction "VCAP_1_31") (pintype "power_in"))
    )
    (net (code "62") (name "Net-(U4-VCAP_2)") (class "Default")
      (node (ref "C22") (pin "2") (pinfunction "2_2") (pintype "passive"))
      (node (ref "U4") (pin "47") (pinfunction "VCAP_2_47") (pintype "power_in"))
    )
    (net (code "63") (name "VDDA") (class "Default")
      (node (ref "C31") (pin "1") (pinfunction "1_1") (pintype "passive"))
      (node (ref "L2") (pin "2") (pinfunction "2_2") (pintype "passive"))
      (node (ref "U4") (pin "13") (pinfunction "VDDA_13") (pintype "power_in"))
    )
    (net (code "64") (name "unconnected-(J9-Pad1)") (class "Default")
      (node (ref "J9") (pin "1") (pinfunction "1_1") (pintype "passive"))
    )
    (net (code "65") (name "unconnected-(U1-ENA-Pad5)") (class "Default")
      (node (ref "U1") (pin "5") (pinfunction "ENA_5") (pintype "passive"))
    )
    (net (code "66") (name "unconnected-(U1-NC-Pad2)") (class "Default")
      (node (ref "U1") (pin "2") (pinfunction "NC_2") (pintype "passive"))
    )
    (net (code "67") (name "unconnected-(U1-NC-Pad3)") (class "Default")
      (node (ref "U1") (pin "3") (pinfunction "NC_3") (pintype "passive"))
    )
    (net (code "68") (name "unconnected-(U4-OSC_OUT{slash}PD1-Pad6)") (class "Default")
      (node (ref "U4") (pin "6") (pinfunction "OSC_OUT/PD1_6") (pintype "passive+no_connect"))
    )
    (net (code "69") (name "unconnected-(U4-PA0-WKUP-Pad14)") (class "Default")
      (node (ref "U4") (pin "14") (pinfunction "PA0-WKUP_14") (pintype "bidirectional"))
    )
    (net (code "70") (name "unconnected-(U4-PA1-Pad15)") (class "Default")
      (node (ref "U4") (pin "15") (pinfunction "PA1_15") (pintype "bidirectional"))
    )
    (net (code "71") (name "unconnected-(U4-PA2-Pad16)") (class "Default")
      (node (ref "U4") (pin "16") (pinfunction "PA2_16") (pintype "bidirectional"))
    )
    (net (code "72") (name "unconnected-(U4-PA11-Pad44)") (class "Default")
      (node (ref "U4") (pin "44") (pinfunction "PA11_44") (pintype "bidirectional"))
    )
    (net (code "73") (name "unconnected-(U4-PA12-Pad45)") (class "Default")
      (node (ref "U4") (pin "45") (pinfunction "PA12_45") (pintype "bidirectional"))
    )
    (net (code "74") (name "unconnected-(U4-PA15{slash}JTDI-Pad50)") (class "Default")
      (node (ref "U4") (pin "50") (pinfunction "PA15/JTDI_50") (pintype "bidirectional"))
    )
    (net (code "75") (name "unconnected-(U4-PB4{slash}JNTRST-Pad56)") (class "Default")
      (node (ref "U4") (pin "56") (pinfunction "PB4/JNTRST_56") (pintype "bidirectional"))
    )
    (net (code "76") (name "unconnected-(U4-PB7-Pad59)") (class "Default")
      (node (ref "U4") (pin "59") (pinfunction "PB7_59") (pintype "bidirectional"))
    )
    (net (code "77") (name "unconnected-(U4-PB10-Pad29)") (class "Default")
      (node (ref "U4") (pin "29") (pinfunction "PB10_29") (pintype "bidirectional"))
    )
    (net (code "78") (name "unconnected-(U4-PB11-Pad30)") (class "Default")
      (node (ref "U4") (pin "30") (pinfunction "PB11_30") (pintype "bidirectional"))
    )
    (net (code "79") (name "unconnected-(U4-PC0-Pad8)") (class "Default")
      (node (ref "U4") (pin "8") (pinfunction "PC0_8") (pintype "bidirectional"))
    )
    (net (code "80") (name "unconnected-(U4-PC1-Pad9)") (class "Default")
      (node (ref "U4") (pin "9") (pinfunction "PC1_9") (pintype "bidirectional"))
    )
    (net (code "81") (name "unconnected-(U4-PC2-Pad10)") (class "Default")
      (node (ref "U4") (pin "10") (pinfunction "PC2_10") (pintype "bidirectional"))
    )
    (net (code "82") (name "unconnected-(U4-PC3-Pad11)") (class "Default")
      (node (ref "U4") (pin "11") (pinfunction "PC3_11") (pintype "bidirectional"))
    )
    (net (code "83") (name "unconnected-(U4-PC12-Pad53)") (class "Default")
      (node (ref "U4") (pin "53") (pinfunction "PC12_53") (pintype "bidirectional"))
    )
    (net (code "84") (name "unconnected-(U4-PC13-TAMPER-RTC-Pad2)") (class "Default")
      (node (ref "U4") (pin "2") (pinfunction "PC13-TAMPER-RTC_2") (pintype "bidirectional"))
    )
    (net (code "85") (name "unconnected-(U4-PC14-OSC32_IN-Pad3)") (class "Default")
      (node (ref "U4") (pin "3") (pinfunction "PC14-OSC32_IN_3") (pintype "bidirectional"))
    )
    (net (code "86") (name "unconnected-(U4-PC15-OSC32_OUT-Pad4)") (class "Default")
      (node (ref "U4") (pin "4") (pinfunction "PC15-OSC32_OUT_4") (pintype "bidirectional"))
    )
    (net (code "87") (name "unconnected-(U4-PD2-Pad54)") (class "Default")
      (node (ref "U4") (pin "54") (pinfunction "PD2_54") (pintype "bidirectional"))
    )
  )
)
